# wbo2_1A.net
KiCad netlist of a schematic drawn in EAGLE
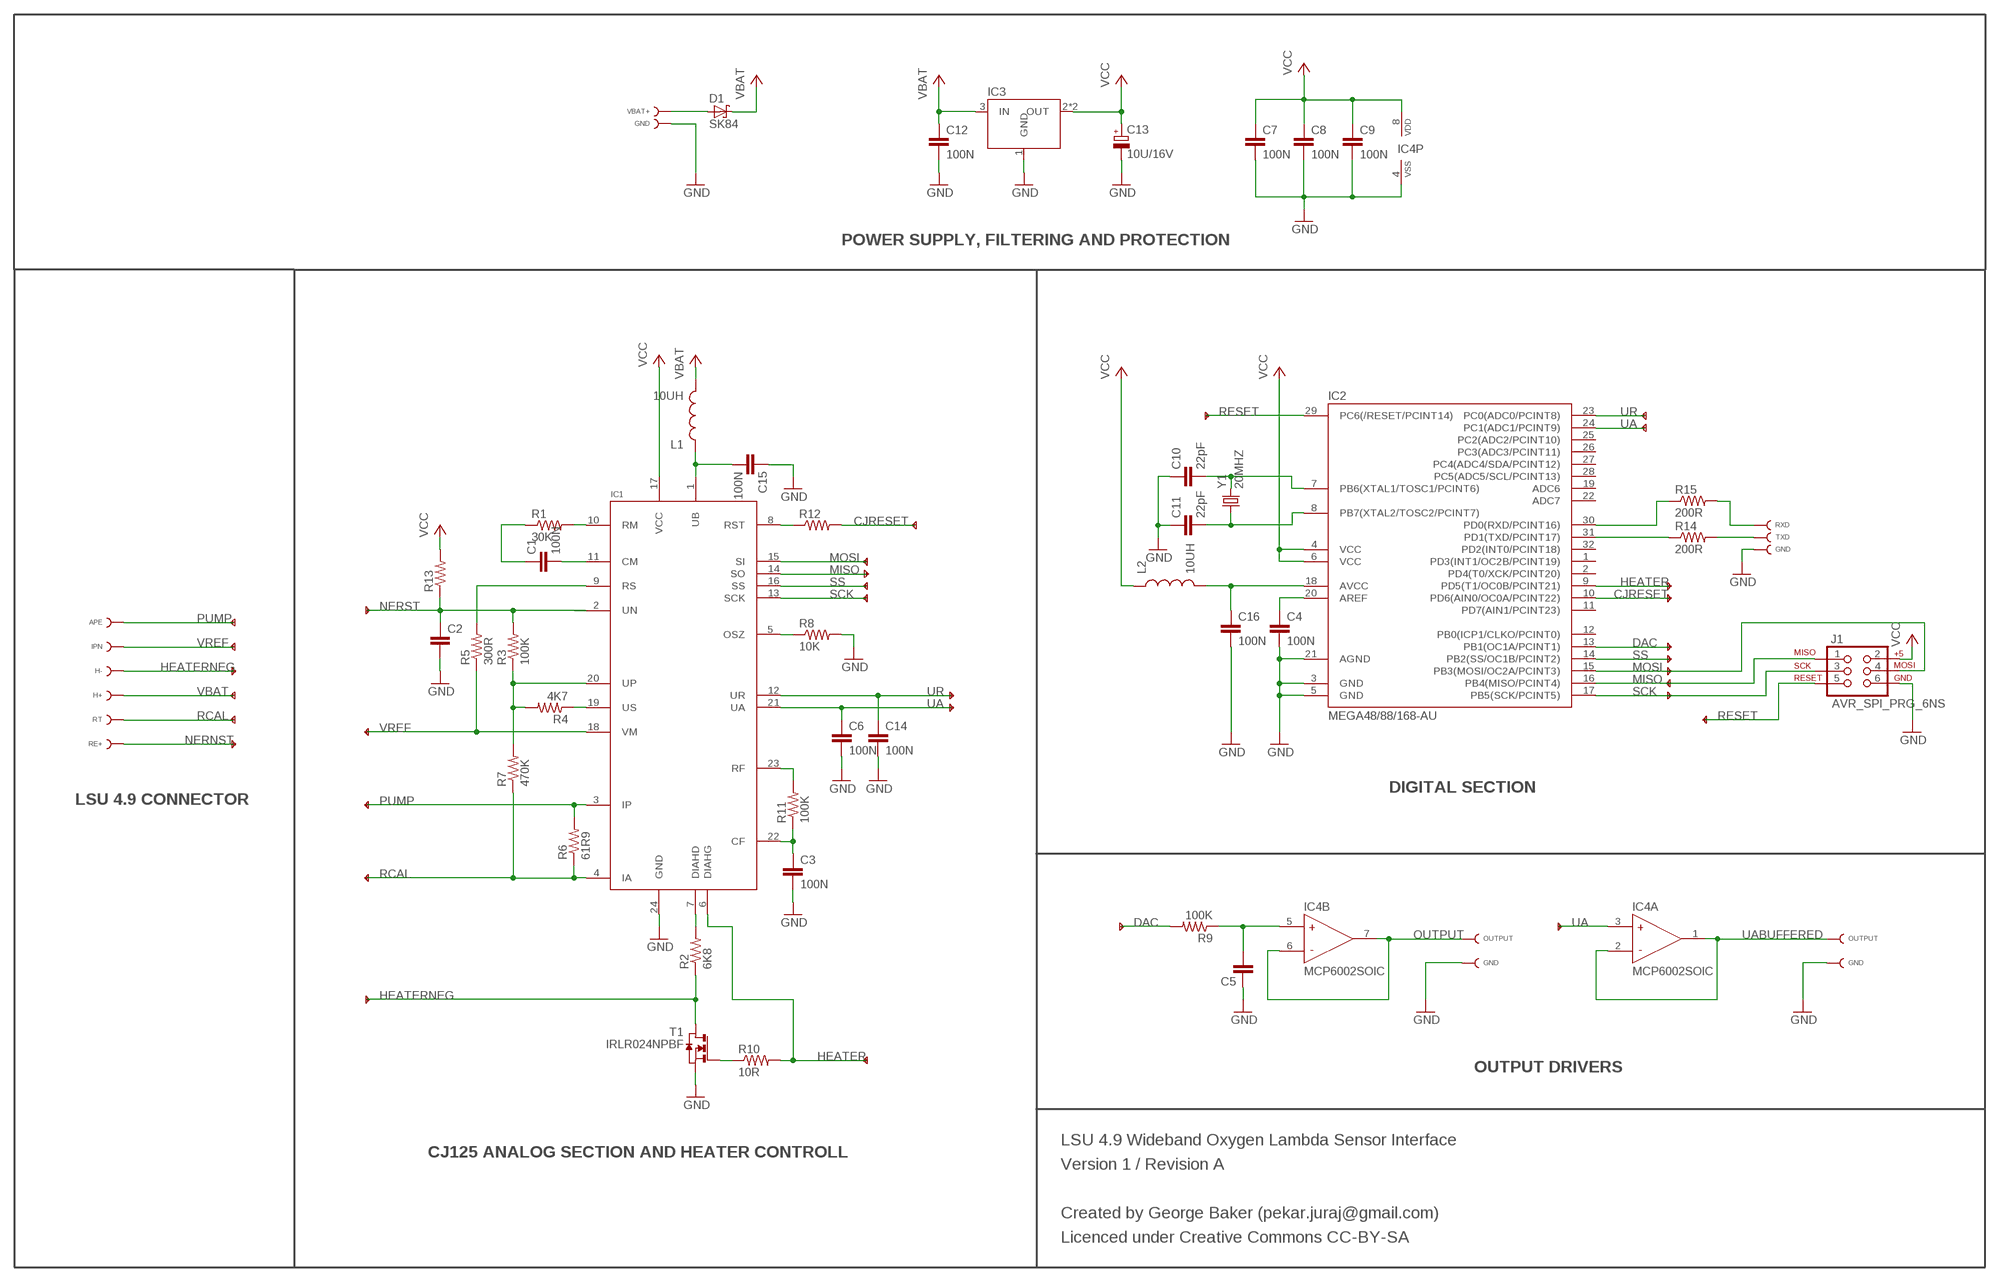
[diagram p0: schematic, sheet 1]

(export (version "E")
  (design (tool "Eeschema 10.0.6"))
  (components
    (comp (ref "C1")
      (value "100N")
      (footprint "eagle-import:0805")
      (libsource (lib "eagle-import") (part "CAP0805"))
    )
    (comp (ref "C2")
      (value "CAP0805")
      (footprint "eagle-import:0805")
      (libsource (lib "eagle-import") (part "CAP0805"))
    )
    (comp (ref "C3")
      (value "100N")
      (footprint "eagle-import:0805")
      (libsource (lib "eagle-import") (part "CAP0805"))
    )
    (comp (ref "C4")
      (value "100N")
      (footprint "eagle-import:0805")
      (libsource (lib "eagle-import") (part "CAP0805"))
    )
    (comp (ref "C5")
      (value "CAP0805")
      (footprint "eagle-import:0805")
      (libsource (lib "eagle-import") (part "CAP0805"))
    )
    (comp (ref "C6")
      (value "100N")
      (footprint "eagle-import:0805")
      (libsource (lib "eagle-import") (part "CAP0805"))
    )
    (comp (ref "C7")
      (value "100N")
      (footprint "eagle-import:0805")
      (libsource (lib "eagle-import") (part "CAP0805"))
    )
    (comp (ref "C8")
      (value "100N")
      (footprint "eagle-import:0805")
      (libsource (lib "eagle-import") (part "CAP0805"))
    )
    (comp (ref "C9")
      (value "100N")
      (footprint "eagle-import:0805")
      (libsource (lib "eagle-import") (part "CAP0805"))
    )
    (comp (ref "C10")
      (value "22pF")
      (footprint "eagle-import:0805")
      (libsource (lib "eagle-import") (part "CAP0805"))
    )
    (comp (ref "C11")
      (value "22pF")
      (footprint "eagle-import:0805")
      (libsource (lib "eagle-import") (part "CAP0805"))
    )
    (comp (ref "C12")
      (value "100N")
      (footprint "eagle-import:0805")
      (libsource (lib "eagle-import") (part "CAP0805"))
    )
    (comp (ref "C13")
      (value "10U/16V")
      (footprint "eagle-import:SMC_A")
      (libsource (lib "eagle-import") (part "CPOL-EUSMCA"))
    )
    (comp (ref "C14")
      (value "100N")
      (footprint "eagle-import:0805")
      (libsource (lib "eagle-import") (part "CAP0805"))
    )
    (comp (ref "C15")
      (value "100N")
      (footprint "eagle-import:0805")
      (libsource (lib "eagle-import") (part "CAP0805"))
    )
    (comp (ref "C16")
      (value "100N")
      (footprint "eagle-import:0805")
      (libsource (lib "eagle-import") (part "CAP0805"))
    )
    (comp (ref "D1")
      (value "SK84")
      (footprint "eagle-import:SMC")
      (libsource (lib "eagle-import") (part "SCHOTTKY-DIODESMC"))
    )
    (comp (ref "IC1")
      (value "CJ125_SOIC24")
      (footprint "eagle-import:SO24W")
      (libsource (lib "eagle-import") (part "CJ125_SOIC24"))
    )
    (comp (ref "IC2")
      (value "MEGA48/88/168-AU")
      (footprint "eagle-import:TQFP32-08")
      (libsource (lib "eagle-import") (part "MEGA48/88/168-AU"))
    )
    (comp (ref "IC3")
      (value "REG1117_SOT-223")
      (footprint "eagle-import:SOT223")
      (libsource (lib "eagle-import") (part "REG1117_SOT-223"))
    )
    (comp (ref "IC4")
      (value "MCP6002SOIC")
      (footprint "eagle-import:SO8")
      (libsource (lib "eagle-import") (part "MCP6002SOIC"))
    )
    (comp (ref "J1")
      (value "AVR_SPI_PRG_6NS")
      (footprint "eagle-import:2X3-NS")
      (libsource (lib "eagle-import") (part "AVR_SPI_PRG_6NS"))
    )
    (comp (ref "L1")
      (value "10UH")
      (footprint "eagle-import:0805")
      (libsource (lib "eagle-import") (part "INDUCTOR0805"))
    )
    (comp (ref "L2")
      (value "10UH")
      (footprint "eagle-import:0805")
      (libsource (lib "eagle-import") (part "INDUCTOR0805"))
    )
    (comp (ref "PAD1")
      (value "APE")
      (footprint "eagle-import:CONPAD-DUAL-HOLE-1.5MM")
      (libsource (lib "eagle-import") (part "CONPAD-DUAL-HOLE-1.5MM"))
    )
    (comp (ref "PAD2")
      (value "IPN")
      (footprint "eagle-import:CONPAD-DUAL-HOLE-1.5MM")
      (libsource (lib "eagle-import") (part "CONPAD-DUAL-HOLE-1.5MM"))
    )
    (comp (ref "PAD3")
      (value "H-")
      (footprint "eagle-import:CONPAD-DUAL-HOLE-1.5MM")
      (libsource (lib "eagle-import") (part "CONPAD-DUAL-HOLE-1.5MM"))
    )
    (comp (ref "PAD4")
      (value "H+")
      (footprint "eagle-import:CONPAD-DUAL-HOLE-1.5MM")
      (libsource (lib "eagle-import") (part "CONPAD-DUAL-HOLE-1.5MM"))
    )
    (comp (ref "PAD5")
      (value "RT")
      (footprint "eagle-import:CONPAD-DUAL-HOLE-1.5MM")
      (libsource (lib "eagle-import") (part "CONPAD-DUAL-HOLE-1.5MM"))
    )
    (comp (ref "PAD6")
      (value "RE+")
      (footprint "eagle-import:CONPAD-DUAL-HOLE-1.5MM")
      (libsource (lib "eagle-import") (part "CONPAD-DUAL-HOLE-1.5MM"))
    )
    (comp (ref "PAD7")
      (value "VBAT+")
      (footprint "eagle-import:CONPAD-DUAL-HOLE-1.5MM")
      (libsource (lib "eagle-import") (part "CONPAD-DUAL-HOLE-1.5MM"))
    )
    (comp (ref "PAD8")
      (value "GND")
      (footprint "eagle-import:CONPAD-DUAL-HOLE-1.5MM")
      (libsource (lib "eagle-import") (part "CONPAD-DUAL-HOLE-1.5MM"))
    )
    (comp (ref "PAD9")
      (value "RXD")
      (footprint "eagle-import:CONPAD-DUAL-HOLE-1.5MM")
      (libsource (lib "eagle-import") (part "CONPAD-DUAL-HOLE-1.5MM"))
    )
    (comp (ref "PAD10")
      (value "TXD")
      (footprint "eagle-import:CONPAD-DUAL-HOLE-1.5MM")
      (libsource (lib "eagle-import") (part "CONPAD-DUAL-HOLE-1.5MM"))
    )
    (comp (ref "PAD11")
      (value "GND")
      (footprint "eagle-import:CONPAD-DUAL-HOLE-1.5MM")
      (libsource (lib "eagle-import") (part "CONPAD-DUAL-HOLE-1.5MM"))
    )
    (comp (ref "PAD12")
      (value "OUTPUT")
      (footprint "eagle-import:CONPAD-DUAL-HOLE-1.5MM")
      (libsource (lib "eagle-import") (part "CONPAD-DUAL-HOLE-1.5MM"))
    )
    (comp (ref "PAD13")
      (value "GND")
      (footprint "eagle-import:CONPAD-DUAL-HOLE-1.5MM")
      (libsource (lib "eagle-import") (part "CONPAD-DUAL-HOLE-1.5MM"))
    )
    (comp (ref "PAD14")
      (value "OUTPUT")
      (footprint "eagle-import:CONPAD-DUAL-HOLE-1.5MM")
      (libsource (lib "eagle-import") (part "CONPAD-DUAL-HOLE-1.5MM"))
    )
    (comp (ref "PAD15")
      (value "GND")
      (footprint "eagle-import:CONPAD-DUAL-HOLE-1.5MM")
      (libsource (lib "eagle-import") (part "CONPAD-DUAL-HOLE-1.5MM"))
    )
    (comp (ref "R1")
      (value "30K")
      (footprint "eagle-import:0805")
      (libsource (lib "eagle-import") (part "RESISTOR0805-RES"))
    )
    (comp (ref "R2")
      (value "6K8")
      (footprint "eagle-import:0805")
      (libsource (lib "eagle-import") (part "RESISTOR0805-RES"))
    )
    (comp (ref "R3")
      (value "100K")
      (footprint "eagle-import:0805")
      (libsource (lib "eagle-import") (part "RESISTOR0805-RES"))
    )
    (comp (ref "R4")
      (value "4K7")
      (footprint "eagle-import:0805")
      (libsource (lib "eagle-import") (part "RESISTOR0805-RES"))
    )
    (comp (ref "R5")
      (value "300R")
      (footprint "eagle-import:0805")
      (libsource (lib "eagle-import") (part "RESISTOR0805-RES"))
    )
    (comp (ref "R6")
      (value "61R9")
      (footprint "eagle-import:0805")
      (libsource (lib "eagle-import") (part "RESISTOR0805-RES"))
    )
    (comp (ref "R7")
      (value "470K")
      (footprint "eagle-import:0805")
      (libsource (lib "eagle-import") (part "RESISTOR0805-RES"))
    )
    (comp (ref "R8")
      (value "10K")
      (footprint "eagle-import:0805")
      (libsource (lib "eagle-import") (part "RESISTOR0805-RES"))
    )
    (comp (ref "R9")
      (value "100K")
      (footprint "eagle-import:0805")
      (libsource (lib "eagle-import") (part "RESISTOR0805-RES"))
    )
    (comp (ref "R10")
      (value "10R")
      (footprint "eagle-import:0805")
      (libsource (lib "eagle-import") (part "RESISTOR0805-RES"))
    )
    (comp (ref "R11")
      (value "100K")
      (footprint "eagle-import:0805")
      (libsource (lib "eagle-import") (part "RESISTOR0805-RES"))
    )
    (comp (ref "R12")
      (value "RESISTOR0805-RES")
      (footprint "eagle-import:0805")
      (libsource (lib "eagle-import") (part "RESISTOR0805-RES"))
    )
    (comp (ref "R13")
      (value "RESISTOR0805-RES")
      (footprint "eagle-import:0805")
      (libsource (lib "eagle-import") (part "RESISTOR0805-RES"))
    )
    (comp (ref "R14")
      (value "200R")
      (footprint "eagle-import:0805")
      (libsource (lib "eagle-import") (part "RESISTOR0805-RES"))
    )
    (comp (ref "R15")
      (value "200R")
      (footprint "eagle-import:0805")
      (libsource (lib "eagle-import") (part "RESISTOR0805-RES"))
    )
    (comp (ref "T1")
      (value "IRLR024NPBF")
      (footprint "eagle-import:TO252")
      (libsource (lib "eagle-import") (part "NMOSFET_TO252"))
    )
    (comp (ref "Y1")
      (value "20MHZ")
      (footprint "eagle-import:CRYSTAL_ILCX13")
      (libsource (lib "eagle-import") (part "CRYSTAL_ILCX13"))
    )
  )
  (nets
    (net (code "1") (name "/CJRESET") (class "Default")
      (node (ref "IC2") (pin "10") (pinfunction "PD6(AIN0/OC0A/PCINT22)_10") (pintype "bidirectional"))
      (node (ref "R12") (pin "2") (pinfunction "2_2") (pintype "passive"))
    )
    (net (code "2") (name "/DAC") (class "Default")
      (node (ref "IC2") (pin "13") (pinfunction "PB1(OC1A/PCINT1)_13") (pintype "bidirectional"))
      (node (ref "R9") (pin "2") (pinfunction "2_2") (pintype "passive"))
    )
    (net (code "3") (name "/HEATER") (class "Default")
      (node (ref "IC1") (pin "6") (pinfunction "DIAHG_6") (pintype "input"))
      (node (ref "IC2") (pin "9") (pinfunction "PD5(T1/OC0B/PCINT21)_9") (pintype "bidirectional"))
      (node (ref "R10") (pin "2") (pinfunction "2_2") (pintype "passive"))
    )
    (net (code "4") (name "/HEATERNEG") (class "Default")
      (node (ref "PAD3") (pin "P$1@1") (pinfunction "P$1_P$1@1") (pintype "passive"))
      (node (ref "PAD3") (pin "P$1@2") (pinfunction "P$1_P$1@2") (pintype "passive"))
      (node (ref "R2") (pin "1") (pinfunction "1_1") (pintype "passive"))
      (node (ref "T1") (pin "3") (pinfunction "D_3") (pintype "passive"))
    )
    (net (code "5") (name "/MISO") (class "Default")
      (node (ref "IC1") (pin "14") (pinfunction "SO_14") (pintype "bidirectional"))
      (node (ref "IC2") (pin "16") (pinfunction "PB4(MISO/PCINT4)_16") (pintype "bidirectional"))
      (node (ref "J1") (pin "1") (pinfunction "1_1") (pintype "passive"))
    )
    (net (code "6") (name "/MOSI") (class "Default")
      (node (ref "IC1") (pin "15") (pinfunction "SI_15") (pintype "bidirectional"))
      (node (ref "IC2") (pin "15") (pinfunction "PB3(MOSI/OC2A/PCINT3)_15") (pintype "bidirectional"))
      (node (ref "J1") (pin "4") (pinfunction "4_4") (pintype "passive"))
    )
    (net (code "7") (name "/NERNST") (class "Default")
      (node (ref "PAD6") (pin "P$1@1") (pinfunction "P$1_P$1@1") (pintype "passive"))
      (node (ref "PAD6") (pin "P$1@2") (pinfunction "P$1_P$1@2") (pintype "passive"))
    )
    (net (code "8") (name "/NERST") (class "Default")
      (node (ref "C2") (pin "1") (pinfunction "1_1") (pintype "passive"))
      (node (ref "IC1") (pin "2") (pinfunction "UN_2") (pintype "bidirectional"))
      (node (ref "R13") (pin "1") (pinfunction "1_1") (pintype "passive"))
      (node (ref "R3") (pin "2") (pinfunction "2_2") (pintype "passive"))
    )
    (net (code "9") (name "/OUTPUT") (class "Default")
      (node (ref "IC4") (pin "6") (pinfunction "INV_6") (pintype "input"))
      (node (ref "IC4") (pin "7") (pinfunction "OUT_7") (pintype "output"))
      (node (ref "PAD12") (pin "P$1@1") (pinfunction "P$1_P$1@1") (pintype "passive"))
      (node (ref "PAD12") (pin "P$1@2") (pinfunction "P$1_P$1@2") (pintype "passive"))
    )
    (net (code "10") (name "/PUMP") (class "Default")
      (node (ref "IC1") (pin "3") (pinfunction "IP_3") (pintype "bidirectional"))
      (node (ref "PAD1") (pin "P$1@1") (pinfunction "P$1_P$1@1") (pintype "passive"))
      (node (ref "PAD1") (pin "P$1@2") (pinfunction "P$1_P$1@2") (pintype "passive"))
      (node (ref "R6") (pin "2") (pinfunction "2_2") (pintype "passive"))
    )
    (net (code "11") (name "/RCAL") (class "Default")
      (node (ref "IC1") (pin "4") (pinfunction "IA_4") (pintype "bidirectional"))
      (node (ref "PAD5") (pin "P$1@1") (pinfunction "P$1_P$1@1") (pintype "passive"))
      (node (ref "PAD5") (pin "P$1@2") (pinfunction "P$1_P$1@2") (pintype "passive"))
      (node (ref "R6") (pin "1") (pinfunction "1_1") (pintype "passive"))
      (node (ref "R7") (pin "1") (pinfunction "1_1") (pintype "passive"))
    )
    (net (code "12") (name "/RESET") (class "Default")
      (node (ref "IC2") (pin "29") (pinfunction "PC6(/RESET/PCINT14)_29") (pintype "bidirectional"))
      (node (ref "J1") (pin "5") (pinfunction "5_5") (pintype "passive"))
    )
    (net (code "13") (name "/SCK") (class "Default")
      (node (ref "IC1") (pin "13") (pinfunction "SCK_13") (pintype "bidirectional"))
      (node (ref "IC2") (pin "17") (pinfunction "PB5(SCK/PCINT5)_17") (pintype "bidirectional"))
      (node (ref "J1") (pin "3") (pinfunction "3_3") (pintype "passive"))
    )
    (net (code "14") (name "/SS") (class "Default")
      (node (ref "IC1") (pin "16") (pinfunction "SS_16") (pintype "bidirectional"))
      (node (ref "IC2") (pin "14") (pinfunction "PB2(SS/OC1B/PCINT2)_14") (pintype "bidirectional"))
    )
    (net (code "15") (name "/UA") (class "Default")
      (node (ref "C6") (pin "1") (pinfunction "1_1") (pintype "passive"))
      (node (ref "IC1") (pin "21") (pinfunction "UA_21") (pintype "bidirectional"))
      (node (ref "IC2") (pin "24") (pinfunction "PC1(ADC1/PCINT9)_24") (pintype "bidirectional"))
      (node (ref "IC4") (pin "3") (pinfunction "NONINV_3") (pintype "input"))
    )
    (net (code "16") (name "/UABUFFERED") (class "Default")
      (node (ref "IC4") (pin "1") (pinfunction "OUT_1") (pintype "output"))
      (node (ref "IC4") (pin "2") (pinfunction "INV_2") (pintype "input"))
      (node (ref "PAD14") (pin "P$1@1") (pinfunction "P$1_P$1@1") (pintype "passive"))
      (node (ref "PAD14") (pin "P$1@2") (pinfunction "P$1_P$1@2") (pintype "passive"))
    )
    (net (code "17") (name "/UR") (class "Default")
      (node (ref "C14") (pin "1") (pinfunction "1_1") (pintype "passive"))
      (node (ref "IC1") (pin "12") (pinfunction "UR_12") (pintype "bidirectional"))
      (node (ref "IC2") (pin "23") (pinfunction "PC0(ADC0/PCINT8)_23") (pintype "bidirectional"))
    )
    (net (code "18") (name "/VREF") (class "Default")
      (node (ref "IC1") (pin "18") (pinfunction "VM_18") (pintype "bidirectional"))
      (node (ref "PAD2") (pin "P$1@1") (pinfunction "P$1_P$1@1") (pintype "passive"))
      (node (ref "PAD2") (pin "P$1@2") (pinfunction "P$1_P$1@2") (pintype "passive"))
      (node (ref "R5") (pin "1") (pinfunction "1_1") (pintype "passive"))
    )
    (net (code "19") (name "GND") (class "Default")
      (node (ref "C10") (pin "1") (pinfunction "1_1") (pintype "passive"))
      (node (ref "C11") (pin "1") (pinfunction "1_1") (pintype "passive"))
      (node (ref "C12") (pin "2") (pinfunction "2_2") (pintype "passive"))
      (node (ref "C13") (pin "-") (pinfunction "-_-") (pintype "passive"))
      (node (ref "C14") (pin "2") (pinfunction "2_2") (pintype "passive"))
      (node (ref "C15") (pin "1") (pinfunction "1_1") (pintype "passive"))
      (node (ref "C16") (pin "2") (pinfunction "2_2") (pintype "passive"))
      (node (ref "C2") (pin "2") (pinfunction "2_2") (pintype "passive"))
      (node (ref "C3") (pin "2") (pinfunction "2_2") (pintype "passive"))
      (node (ref "C4") (pin "2") (pinfunction "2_2") (pintype "passive"))
      (node (ref "C5") (pin "1") (pinfunction "1_1") (pintype "passive"))
      (node (ref "C6") (pin "2") (pinfunction "2_2") (pintype "passive"))
      (node (ref "C7") (pin "2") (pinfunction "2_2") (pintype "passive"))
      (node (ref "C8") (pin "2") (pinfunction "2_2") (pintype "passive"))
      (node (ref "C9") (pin "2") (pinfunction "2_2") (pintype "passive"))
      (node (ref "IC1") (pin "24") (pinfunction "GND_24") (pintype "power_in"))
      (node (ref "IC2") (pin "21") (pinfunction "AGND_21") (pintype "power_in"))
      (node (ref "IC2") (pin "3") (pinfunction "GND_3") (pintype "power_in"))
      (node (ref "IC2") (pin "5") (pinfunction "GND_5") (pintype "power_in"))
      (node (ref "IC3") (pin "1") (pinfunction "GND_1") (pintype "bidirectional"))
      (node (ref "IC4") (pin "4") (pinfunction "VSS_4") (pintype "bidirectional"))
      (node (ref "J1") (pin "6") (pinfunction "6_6") (pintype "passive"))
      (node (ref "PAD11") (pin "P$1@1") (pinfunction "P$1_P$1@1") (pintype "passive"))
      (node (ref "PAD11") (pin "P$1@2") (pinfunction "P$1_P$1@2") (pintype "passive"))
      (node (ref "PAD13") (pin "P$1@1") (pinfunction "P$1_P$1@1") (pintype "passive"))
      (node (ref "PAD13") (pin "P$1@2") (pinfunction "P$1_P$1@2") (pintype "passive"))
      (node (ref "PAD15") (pin "P$1@1") (pinfunction "P$1_P$1@1") (pintype "passive"))
      (node (ref "PAD15") (pin "P$1@2") (pinfunction "P$1_P$1@2") (pintype "passive"))
      (node (ref "PAD8") (pin "P$1@1") (pinfunction "P$1_P$1@1") (pintype "passive"))
      (node (ref "PAD8") (pin "P$1@2") (pinfunction "P$1_P$1@2") (pintype "passive"))
      (node (ref "R8") (pin "2") (pinfunction "2_2") (pintype "passive"))
      (node (ref "T1") (pin "2") (pinfunction "S_2") (pintype "passive"))
    )
    (net (code "20") (name "Net-(C1-Pad1)") (class "Default")
      (node (ref "C1") (pin "1") (pinfunction "1_1") (pintype "passive"))
      (node (ref "R1") (pin "1") (pinfunction "1_1") (pintype "passive"))
    )
    (net (code "21") (name "Net-(D1-PadA)") (class "Default")
      (node (ref "D1") (pin "A") (pinfunction "A_A") (pintype "passive"))
      (node (ref "PAD7") (pin "P$1@1") (pinfunction "P$1_P$1@1") (pintype "passive"))
      (node (ref "PAD7") (pin "P$1@2") (pinfunction "P$1_P$1@2") (pintype "passive"))
    )
    (net (code "22") (name "Net-(IC1-CF)") (class "Default")
      (node (ref "C3") (pin "1") (pinfunction "1_1") (pintype "passive"))
      (node (ref "IC1") (pin "22") (pinfunction "CF_22") (pintype "bidirectional"))
      (node (ref "R11") (pin "1") (pinfunction "1_1") (pintype "passive"))
    )
    (net (code "23") (name "Net-(IC1-CM)") (class "Default")
      (node (ref "C1") (pin "2") (pinfunction "2_2") (pintype "passive"))
      (node (ref "IC1") (pin "11") (pinfunction "CM_11") (pintype "bidirectional"))
    )
    (net (code "24") (name "Net-(IC1-DIAHD)") (class "Default")
      (node (ref "IC1") (pin "7") (pinfunction "DIAHD_7") (pintype "input"))
      (node (ref "R2") (pin "2") (pinfunction "2_2") (pintype "passive"))
    )
    (net (code "25") (name "Net-(IC1-OSZ)") (class "Default")
      (node (ref "IC1") (pin "5") (pinfunction "OSZ_5") (pintype "bidirectional"))
      (node (ref "R8") (pin "1") (pinfunction "1_1") (pintype "passive"))
    )
    (net (code "26") (name "Net-(IC1-RF)") (class "Default")
      (node (ref "IC1") (pin "23") (pinfunction "RF_23") (pintype "bidirectional"))
      (node (ref "R11") (pin "2") (pinfunction "2_2") (pintype "passive"))
    )
    (net (code "27") (name "Net-(IC1-RM)") (class "Default")
      (node (ref "IC1") (pin "10") (pinfunction "RM_10") (pintype "bidirectional"))
      (node (ref "R1") (pin "2") (pinfunction "2_2") (pintype "passive"))
    )
    (net (code "28") (name "Net-(IC1-RS)") (class "Default")
      (node (ref "IC1") (pin "9") (pinfunction "RS_9") (pintype "bidirectional"))
      (node (ref "R5") (pin "2") (pinfunction "2_2") (pintype "passive"))
    )
    (net (code "29") (name "Net-(IC1-RST)") (class "Default")
      (node (ref "IC1") (pin "8") (pinfunction "RST_8") (pintype "bidirectional"))
      (node (ref "R12") (pin "1") (pinfunction "1_1") (pintype "passive"))
    )
    (net (code "30") (name "Net-(IC1-UB)") (class "Default")
      (node (ref "C15") (pin "2") (pinfunction "2_2") (pintype "passive"))
      (node (ref "IC1") (pin "1") (pinfunction "UB_1") (pintype "power_in"))
      (node (ref "L1") (pin "1") (pinfunction "1_1") (pintype "passive"))
    )
    (net (code "31") (name "Net-(IC1-UP)") (class "Default")
      (node (ref "IC1") (pin "20") (pinfunction "UP_20") (pintype "bidirectional"))
      (node (ref "R3") (pin "1") (pinfunction "1_1") (pintype "passive"))
      (node (ref "R4") (pin "2") (pinfunction "2_2") (pintype "passive"))
      (node (ref "R7") (pin "2") (pinfunction "2_2") (pintype "passive"))
    )
    (net (code "32") (name "Net-(IC1-US)") (class "Default")
      (node (ref "IC1") (pin "19") (pinfunction "US_19") (pintype "bidirectional"))
      (node (ref "R4") (pin "1") (pinfunction "1_1") (pintype "passive"))
    )
    (net (code "33") (name "Net-(IC2-AREF)") (class "Default")
      (node (ref "C4") (pin "1") (pinfunction "1_1") (pintype "passive"))
      (node (ref "IC2") (pin "20") (pinfunction "AREF_20") (pintype "passive"))
    )
    (net (code "34") (name "Net-(IC2-AVCC)") (class "Default")
      (node (ref "C16") (pin "1") (pinfunction "1_1") (pintype "passive"))
      (node (ref "IC2") (pin "18") (pinfunction "AVCC_18") (pintype "passive"))
      (node (ref "L2") (pin "2") (pinfunction "2_2") (pintype "passive"))
    )
    (net (code "35") (name "Net-(IC2-PB6(XTAL1{slash}TOSC1{slash}PCINT6))") (class "Default")
      (node (ref "C10") (pin "2") (pinfunction "2_2") (pintype "passive"))
      (node (ref "IC2") (pin "7") (pinfunction "PB6(XTAL1/TOSC1/PCINT6)_7") (pintype "bidirectional"))
      (node (ref "Y1") (pin "3") (pinfunction "2_3") (pintype "passive"))
    )
    (net (code "36") (name "Net-(IC2-PB7(XTAL2{slash}TOSC2{slash}PCINT7))") (class "Default")
      (node (ref "C11") (pin "2") (pinfunction "2_2") (pintype "passive"))
      (node (ref "IC2") (pin "8") (pinfunction "PB7(XTAL2/TOSC2/PCINT7)_8") (pintype "bidirectional"))
      (node (ref "Y1") (pin "1") (pinfunction "1_1") (pintype "passive"))
    )
    (net (code "37") (name "Net-(IC2-PD0(RXD{slash}PCINT16))") (class "Default")
      (node (ref "IC2") (pin "30") (pinfunction "PD0(RXD/PCINT16)_30") (pintype "bidirectional"))
      (node (ref "R15") (pin "1") (pinfunction "1_1") (pintype "passive"))
    )
    (net (code "38") (name "Net-(IC2-PD1(TXD{slash}PCINT17))") (class "Default")
      (node (ref "IC2") (pin "31") (pinfunction "PD1(TXD/PCINT17)_31") (pintype "bidirectional"))
      (node (ref "R14") (pin "1") (pinfunction "1_1") (pintype "passive"))
    )
    (net (code "39") (name "Net-(IC4B-NONINV)") (class "Default")
      (node (ref "C5") (pin "2") (pinfunction "2_2") (pintype "passive"))
      (node (ref "IC4") (pin "5") (pinfunction "NONINV_5") (pintype "input"))
      (node (ref "R9") (pin "1") (pinfunction "1_1") (pintype "passive"))
    )
    (net (code "40") (name "Net-(PAD9-P$1-PadP$1@1)") (class "Default")
      (node (ref "PAD9") (pin "P$1@1") (pinfunction "P$1_P$1@1") (pintype "passive"))
      (node (ref "PAD9") (pin "P$1@2") (pinfunction "P$1_P$1@2") (pintype "passive"))
      (node (ref "R15") (pin "2") (pinfunction "2_2") (pintype "passive"))
    )
    (net (code "41") (name "Net-(PAD10-P$1-PadP$1@1)") (class "Default")
      (node (ref "PAD10") (pin "P$1@1") (pinfunction "P$1_P$1@1") (pintype "passive"))
      (node (ref "PAD10") (pin "P$1@2") (pinfunction "P$1_P$1@2") (pintype "passive"))
      (node (ref "R14") (pin "2") (pinfunction "2_2") (pintype "passive"))
    )
    (net (code "42") (name "Net-(T1-G)") (class "Default")
      (node (ref "R10") (pin "1") (pinfunction "1_1") (pintype "passive"))
      (node (ref "T1") (pin "1") (pinfunction "G_1") (pintype "passive"))
    )
    (net (code "43") (name "VBAT") (class "Default")
      (node (ref "C12") (pin "1") (pinfunction "1_1") (pintype "passive"))
      (node (ref "D1") (pin "C") (pinfunction "C_C") (pintype "passive"))
      (node (ref "IC3") (pin "3") (pinfunction "IN_3") (pintype "power_in"))
      (node (ref "L1") (pin "2") (pinfunction "2_2") (pintype "passive"))
      (node (ref "PAD4") (pin "P$1@1") (pinfunction "P$1_P$1@1") (pintype "passive"))
      (node (ref "PAD4") (pin "P$1@2") (pinfunction "P$1_P$1@2") (pintype "passive"))
    )
    (net (code "44") (name "VCC") (class "Default")
      (node (ref "C13") (pin "+") (pinfunction "+_+") (pintype "passive"))
      (node (ref "C7") (pin "1") (pinfunction "1_1") (pintype "passive"))
      (node (ref "C8") (pin "1") (pinfunction "1_1") (pintype "passive"))
      (node (ref "C9") (pin "1") (pinfunction "1_1") (pintype "passive"))
      (node (ref "IC1") (pin "17") (pinfunction "VCC_17") (pintype "power_in"))
      (node (ref "IC2") (pin "4") (pinfunction "VCC_4") (pintype "power_in"))
      (node (ref "IC2") (pin "6") (pinfunction "VCC_6") (pintype "power_in"))
      (node (ref "IC3") (pin "2") (pinfunction "OUT_2") (pintype "power_in"))
      (node (ref "IC3") (pin "4") (pinfunction "OUT_4") (pintype "power_in"))
      (node (ref "IC4") (pin "8") (pinfunction "VDD_8") (pintype "bidirectional"))
      (node (ref "J1") (pin "2") (pinfunction "2_2") (pintype "passive"))
      (node (ref "L2") (pin "1") (pinfunction "1_1") (pintype "passive"))
      (node (ref "R13") (pin "2") (pinfunction "2_2") (pintype "passive"))
    )
    (net (code "45") (name "unconnected-(IC2-ADC6-Pad19)") (class "Default")
      (node (ref "IC2") (pin "19") (pinfunction "ADC6_19") (pintype "passive"))
    )
    (net (code "46") (name "unconnected-(IC2-ADC7-Pad22)") (class "Default")
      (node (ref "IC2") (pin "22") (pinfunction "ADC7_22") (pintype "passive"))
    )
    (net (code "47") (name "unconnected-(IC2-PB0(ICP1{slash}CLKO{slash}PCINT0)-Pad12)") (class "Default")
      (node (ref "IC2") (pin "12") (pinfunction "PB0(ICP1/CLKO/PCINT0)_12") (pintype "bidirectional"))
    )
    (net (code "48") (name "unconnected-(IC2-PC2(ADC2{slash}PCINT10)-Pad25)") (class "Default")
      (node (ref "IC2") (pin "25") (pinfunction "PC2(ADC2/PCINT10)_25") (pintype "bidirectional"))
    )
    (net (code "49") (name "unconnected-(IC2-PC3(ADC3{slash}PCINT11)-Pad26)") (class "Default")
      (node (ref "IC2") (pin "26") (pinfunction "PC3(ADC3/PCINT11)_26") (pintype "bidirectional"))
    )
    (net (code "50") (name "unconnected-(IC2-PC4(ADC4{slash}SDA{slash}PCINT12)-Pad27)") (class "Default")
      (node (ref "IC2") (pin "27") (pinfunction "PC4(ADC4/SDA/PCINT12)_27") (pintype "bidirectional"))
    )
    (net (code "51") (name "unconnected-(IC2-PC5(ADC5{slash}SCL{slash}PCINT13)-Pad28)") (class "Default")
      (node (ref "IC2") (pin "28") (pinfunction "PC5(ADC5/SCL/PCINT13)_28") (pintype "bidirectional"))
    )
    (net (code "52") (name "unconnected-(IC2-PD2(INT0{slash}PCINT18)-Pad32)") (class "Default")
      (node (ref "IC2") (pin "32") (pinfunction "PD2(INT0/PCINT18)_32") (pintype "bidirectional"))
    )
    (net (code "53") (name "unconnected-(IC2-PD3(INT1{slash}OC2B{slash}PCINT19)-Pad1)") (class "Default")
      (node (ref "IC2") (pin "1") (pinfunction "PD3(INT1/OC2B/PCINT19)_1") (pintype "bidirectional"))
    )
    (net (code "54") (name "unconnected-(IC2-PD4(T0{slash}XCK{slash}PCINT20)-Pad2)") (class "Default")
      (node (ref "IC2") (pin "2") (pinfunction "PD4(T0/XCK/PCINT20)_2") (pintype "bidirectional"))
    )
    (net (code "55") (name "unconnected-(IC2-PD7(AIN1{slash}PCINT23)-Pad11)") (class "Default")
      (node (ref "IC2") (pin "11") (pinfunction "PD7(AIN1/PCINT23)_11") (pintype "bidirectional"))
    )
  )
)
